# STM32.net
KiCad netlist of a schematic drawn in Altium Designer
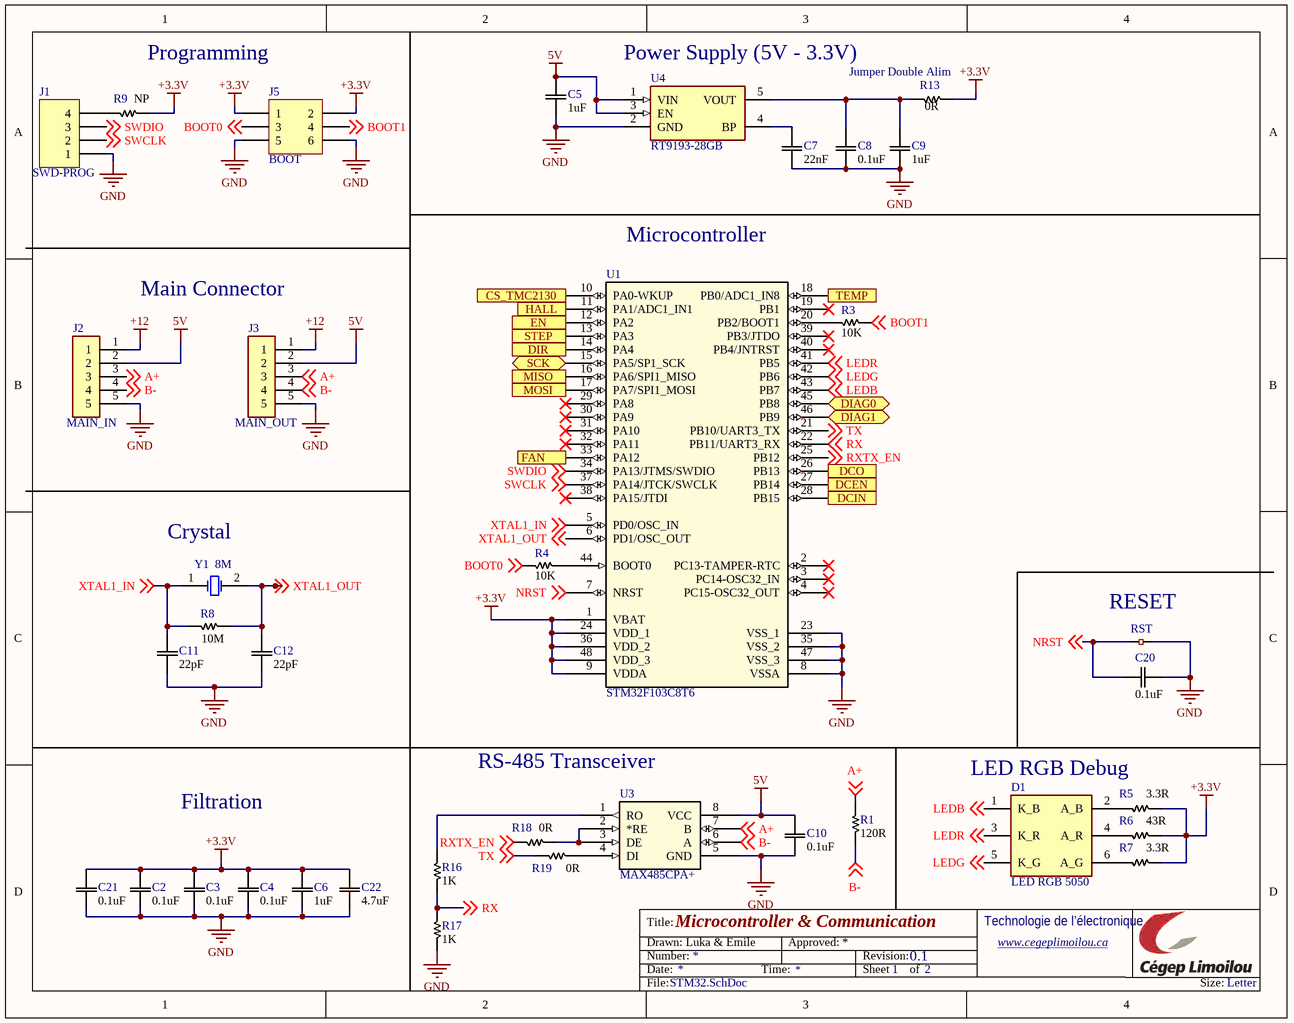
[diagram p0: STM32.SchDoc]

(export (version "E")
  (design (tool "Eeschema 10.0.6"))
  (components
    (comp (ref "C2")
      (value "0.1uF")
      (footprint "0603")
      (description "Capacitor SMD 0603")
      (fields
        (field (name "MANUFACTURER_PART_NUMBER") "12065A820JAT2A")
        (field (name "Comment") "Capacitor SMD")
        (field (name "COPYRIGHT") "Copyright (C) 2018 Accelerated Designs. All rights reserved")
      )
      (libsource (lib "Schematic_Emile") (part "Capacitor SMD"))
    )
    (comp (ref "C3")
      (value "0.1uF")
      (footprint "0603")
      (description "Capacitor SMD 0603")
      (fields
        (field (name "MANUFACTURER_PART_NUMBER") "12065A820JAT2A")
        (field (name "Comment") "Capacitor SMD")
        (field (name "COPYRIGHT") "Copyright (C) 2018 Accelerated Designs. All rights reserved")
      )
      (libsource (lib "Schematic_Emile") (part "Capacitor SMD"))
    )
    (comp (ref "C4")
      (value "0.1uF")
      (footprint "0603")
      (description "Capacitor SMD 0603")
      (fields
        (field (name "MANUFACTURER_PART_NUMBER") "12065A820JAT2A")
        (field (name "Comment") "Capacitor SMD")
        (field (name "COPYRIGHT") "Copyright (C) 2018 Accelerated Designs. All rights reserved")
      )
      (libsource (lib "Schematic_Emile") (part "Capacitor SMD"))
    )
    (comp (ref "C5")
      (value "1uF")
      (footprint "0603")
      (description "Capacitor SMD 0603")
      (fields
        (field (name "MANUFACTURER_PART_NUMBER") "12065A820JAT2A")
        (field (name "Comment") "Capacitor SMD")
        (field (name "COPYRIGHT") "Copyright (C) 2018 Accelerated Designs. All rights reserved")
      )
      (libsource (lib "Schematic_Emile") (part "Capacitor SMD"))
    )
    (comp (ref "C6")
      (value "1uF")
      (footprint "0603")
      (description "Capacitor SMD 0603")
      (fields
        (field (name "MANUFACTURER_PART_NUMBER") "12065A820JAT2A")
        (field (name "Comment") "Capacitor SMD")
        (field (name "COPYRIGHT") "Copyright (C) 2018 Accelerated Designs. All rights reserved")
      )
      (libsource (lib "Schematic_Emile") (part "Capacitor SMD"))
    )
    (comp (ref "C7")
      (value "22nF")
      (footprint "0603")
      (description "Capacitor SMD 0603")
      (fields
        (field (name "MANUFACTURER_PART_NUMBER") "12065A820JAT2A")
        (field (name "Comment") "Capacitor SMD")
        (field (name "COPYRIGHT") "Copyright (C) 2018 Accelerated Designs. All rights reserved")
      )
      (libsource (lib "Schematic_Emile") (part "Capacitor SMD"))
    )
    (comp (ref "C8")
      (value "0.1uF")
      (footprint "0603")
      (description "Capacitor SMD 0603")
      (fields
        (field (name "MANUFACTURER_PART_NUMBER") "12065A820JAT2A")
        (field (name "Comment") "Capacitor SMD")
        (field (name "COPYRIGHT") "Copyright (C) 2018 Accelerated Designs. All rights reserved")
      )
      (libsource (lib "Schematic_Emile") (part "Capacitor SMD"))
    )
    (comp (ref "C9")
      (value "1uF")
      (footprint "0603")
      (description "Capacitor SMD 0603")
      (fields
        (field (name "MANUFACTURER_PART_NUMBER") "12065A820JAT2A")
        (field (name "Comment") "Capacitor SMD")
        (field (name "COPYRIGHT") "Copyright (C) 2018 Accelerated Designs. All rights reserved")
      )
      (libsource (lib "Schematic_Emile") (part "Capacitor SMD"))
    )
    (comp (ref "C10")
      (value "0.1uF")
      (footprint "0603")
      (description "Capacitor SMD 0603")
      (fields
        (field (name "MANUFACTURER_PART_NUMBER") "12065A820JAT2A")
        (field (name "Comment") "Capacitor SMD")
        (field (name "COPYRIGHT") "Copyright (C) 2018 Accelerated Designs. All rights reserved")
      )
      (libsource (lib "Schematic_Emile") (part "Capacitor SMD"))
    )
    (comp (ref "C11")
      (value "22pF")
      (footprint "0603")
      (description "Capacitor SMD 0603")
      (fields
        (field (name "MANUFACTURER_PART_NUMBER") "12065A820JAT2A")
        (field (name "Comment") "Capacitor SMD")
        (field (name "COPYRIGHT") "Copyright (C) 2018 Accelerated Designs. All rights reserved")
      )
      (libsource (lib "Schematic_Emile") (part "Capacitor SMD"))
    )
    (comp (ref "C12")
      (value "22pF")
      (footprint "0603")
      (description "Capacitor SMD 0603")
      (fields
        (field (name "MANUFACTURER_PART_NUMBER") "12065A820JAT2A")
        (field (name "Comment") "Capacitor SMD")
        (field (name "COPYRIGHT") "Copyright (C) 2018 Accelerated Designs. All rights reserved")
      )
      (libsource (lib "Schematic_Emile") (part "Capacitor SMD"))
    )
    (comp (ref "C20")
      (value "0.1uF")
      (footprint "0603")
      (description "Capacitor SMD 0603")
      (fields
        (field (name "MANUFACTURER_PART_NUMBER") "12065A820JAT2A")
        (field (name "Comment") "Capacitor SMD")
        (field (name "COPYRIGHT") "Copyright (C) 2018 Accelerated Designs. All rights reserved")
      )
      (libsource (lib "Schematic_Emile") (part "Capacitor SMD"))
    )
    (comp (ref "C21")
      (value "0.1uF")
      (footprint "0603")
      (description "Capacitor SMD 0603")
      (fields
        (field (name "MANUFACTURER_PART_NUMBER") "12065A820JAT2A")
        (field (name "Comment") "Capacitor SMD")
        (field (name "COPYRIGHT") "Copyright (C) 2018 Accelerated Designs. All rights reserved")
      )
      (libsource (lib "Schematic_Emile") (part "Capacitor SMD"))
    )
    (comp (ref "C22")
      (value "4.7uF")
      (footprint "0603")
      (description "Capacitor SMD 0603")
      (fields
        (field (name "MANUFACTURER_PART_NUMBER") "12065A820JAT2A")
        (field (name "Comment") "Capacitor SMD")
        (field (name "COPYRIGHT") "Copyright (C) 2018 Accelerated Designs. All rights reserved")
      )
      (libsource (lib "Schematic_Emile") (part "Capacitor SMD"))
    )
    (comp (ref "D1")
      (value "LED RGB 5050")
      (footprint "LED 5050")
      (description "LED")
      (fields
        (field (name "MANUFACTURER_PART_NUMBER") "150505M173300")
        (field (name "MOUSER PART NUMBER") "710-150505M173300")
      )
      (libsource (lib "Schematic_Emile") (part "150505M173300"))
    )
    (comp (ref "J1")
      (value "SWD-PROG")
      (footprint "HDR1X4")
      (description "Header, 4-Pin")
      (fields (field (name "PUBLISHER") "Altium Limited"))
      (libsource (lib "Miscellaneous Connectors") (part "Header 4"))
    )
    (comp (ref "J2")
      (value "MAIN_IN")
      (footprint "JST 5POS 2.5mm 90°")
      (description "Connector")
      (fields (field (name "MANUFACTURER_PART_NUMBER") "S5B-XH-A-1(LF)(SN)"))
      (libsource (lib "Schematic_Emile") (part "JST 5POS"))
    )
    (comp (ref "J3")
      (value "MAIN_OUT")
      (footprint "JST 5POS 2.5mm 90°")
      (description "Connector")
      (fields (field (name "MANUFACTURER_PART_NUMBER") "S5B-XH-A-1(LF)(SN)"))
      (libsource (lib "Schematic_Emile") (part "JST 5POS"))
    )
    (comp (ref "J5")
      (value "BOOT")
      (footprint "Header 3x2 1.27mm SMD")
      (description "Header, 3-Pin, Dual row")
      (fields (field (name "PUBLISHER") "Altium Limited"))
      (libsource (lib "Miscellaneous Connectors") (part "Header 3X2"))
    )
    (comp (ref "R1")
      (value "120R")
      (footprint "0603")
      (description "Resistor 0603 SMD")
      (fields
        (field (name "MANUFACTURER_PART_NUMBER") "ERJ8CWFR024V")
        (field (name "Comment") "Resistor 0603")
        (field (name "COPYRIGHT") "Copyright (C) 2018 Accelerated Designs. All rights reserved")
      )
      (libsource (lib "Schematic_Emile") (part "Resistor 0603"))
    )
    (comp (ref "R3")
      (value "10K")
      (footprint "0603")
      (description "Resistor 0603 SMD")
      (fields
        (field (name "MANUFACTURER_PART_NUMBER") "ERJ8CWFR024V")
        (field (name "Comment") "Resistor 0603")
        (field (name "COPYRIGHT") "Copyright (C) 2018 Accelerated Designs. All rights reserved")
      )
      (libsource (lib "Schematic_Emile") (part "Resistor 0603"))
    )
    (comp (ref "R4")
      (value "10K")
      (footprint "0603")
      (description "Resistor 0603 SMD")
      (fields
        (field (name "MANUFACTURER_PART_NUMBER") "ERJ8CWFR024V")
        (field (name "Comment") "Resistor 0603")
        (field (name "COPYRIGHT") "Copyright (C) 2018 Accelerated Designs. All rights reserved")
      )
      (libsource (lib "Schematic_Emile") (part "Resistor 0603"))
    )
    (comp (ref "R5")
      (value "3.3R")
      (footprint "0603")
      (description "Resistor 0603 SMD")
      (fields
        (field (name "MANUFACTURER_PART_NUMBER") "ERJ8CWFR024V")
        (field (name "Comment") "Resistor 0603")
        (field (name "COPYRIGHT") "Copyright (C) 2018 Accelerated Designs. All rights reserved")
      )
      (libsource (lib "Schematic_Emile") (part "Resistor 0603"))
    )
    (comp (ref "R6")
      (value "43R")
      (footprint "0603")
      (description "Resistor 0603 SMD")
      (fields
        (field (name "MANUFACTURER_PART_NUMBER") "ERJ8CWFR024V")
        (field (name "Comment") "Resistor 0603")
        (field (name "COPYRIGHT") "Copyright (C) 2018 Accelerated Designs. All rights reserved")
      )
      (libsource (lib "Schematic_Emile") (part "Resistor 0603"))
    )
    (comp (ref "R7")
      (value "3.3R")
      (footprint "0603")
      (description "Resistor 0603 SMD")
      (fields
        (field (name "MANUFACTURER_PART_NUMBER") "ERJ8CWFR024V")
        (field (name "Comment") "Resistor 0603")
        (field (name "COPYRIGHT") "Copyright (C) 2018 Accelerated Designs. All rights reserved")
      )
      (libsource (lib "Schematic_Emile") (part "Resistor 0603"))
    )
    (comp (ref "R8")
      (value "10M")
      (footprint "0603")
      (description "Resistor 0603 SMD")
      (fields
        (field (name "MANUFACTURER_PART_NUMBER") "ERJ8CWFR024V")
        (field (name "Comment") "Resistor 0603")
        (field (name "COPYRIGHT") "Copyright (C) 2018 Accelerated Designs. All rights reserved")
      )
      (libsource (lib "Schematic_Emile") (part "Resistor 0603"))
    )
    (comp (ref "R9")
      (value "NP")
      (footprint "0603")
      (description "Resistor 0603 SMD")
      (fields
        (field (name "MANUFACTURER_PART_NUMBER") "ERJ8CWFR024V")
        (field (name "Comment") "Resistor 0603")
        (field (name "COPYRIGHT") "Copyright (C) 2018 Accelerated Designs. All rights reserved")
      )
      (libsource (lib "Schematic_Emile") (part "Resistor 0603"))
    )
    (comp (ref "R13")
      (value "0R")
      (footprint "0603")
      (description "Resistor 0603 SMD")
      (fields
        (field (name "MANUFACTURER_PART_NUMBER") "ERJ8CWFR024V")
        (field (name "Comment") "Resistor 0603")
        (field (name "COPYRIGHT") "Copyright (C) 2018 Accelerated Designs. All rights reserved")
      )
      (libsource (lib "Schematic_Emile") (part "Resistor 0603"))
    )
    (comp (ref "R16")
      (value "1K")
      (footprint "0603")
      (description "Resistor 0603 SMD")
      (fields
        (field (name "MANUFACTURER_PART_NUMBER") "ERJ8CWFR024V")
        (field (name "Comment") "Resistor 0603")
        (field (name "COPYRIGHT") "Copyright (C) 2018 Accelerated Designs. All rights reserved")
      )
      (libsource (lib "Schematic_Emile") (part "Resistor 0603"))
    )
    (comp (ref "R17")
      (value "1K")
      (footprint "0603")
      (description "Resistor 0603 SMD")
      (fields
        (field (name "MANUFACTURER_PART_NUMBER") "ERJ8CWFR024V")
        (field (name "Comment") "Resistor 0603")
        (field (name "COPYRIGHT") "Copyright (C) 2018 Accelerated Designs. All rights reserved")
      )
      (libsource (lib "Schematic_Emile") (part "Resistor 0603"))
    )
    (comp (ref "R18")
      (value "0R")
      (footprint "0603")
      (description "Resistor 0603 SMD")
      (fields
        (field (name "MANUFACTURER_PART_NUMBER") "ERJ8CWFR024V")
        (field (name "Comment") "Resistor 0603")
        (field (name "COPYRIGHT") "Copyright (C) 2018 Accelerated Designs. All rights reserved")
      )
      (libsource (lib "Schematic_Emile") (part "Resistor 0603"))
    )
    (comp (ref "R19")
      (value "0R")
      (footprint "0603")
      (description "Resistor 0603 SMD")
      (fields
        (field (name "MANUFACTURER_PART_NUMBER") "ERJ8CWFR024V")
        (field (name "Comment") "Resistor 0603")
        (field (name "COPYRIGHT") "Copyright (C) 2018 Accelerated Designs. All rights reserved")
      )
      (libsource (lib "Schematic_Emile") (part "Resistor 0603"))
    )
    (comp (ref "RST")
      (value "PAD RST")
      (footprint "PAD")
      (description "SMD Pad for contact")
      (libsource (lib "Schematic_Emile") (part "PAD"))
    )
    (comp (ref "U1")
      (value "STM32F103C8T6")
      (footprint "LQFP-48")
      (description "Integrated Circuit STM32")
      (fields (field (name "COPYRIGHT") "Copyright (C) 2018 Accelerated Designs. All rights reserved"))
      (libsource (lib "Schematic_Emile") (part "STM32F103C8T6"))
    )
    (comp (ref "U3")
      (value "MAX485CPA+")
      (footprint "DIP 8 - 3D")
      (description "RS485 Communication")
      (fields (field (name "COPYRIGHT") "Copyright (C) 2018 Accelerated Designs. All rights reserved"))
      (libsource (lib "Schematic_Emile") (part "MAX485CPA+"))
    )
    (comp (ref "U4")
      (value "RT9193-28GB")
      (footprint "SamacSys:SOT94P279X130-5N")
      (description "Voltage Regulator 3.3V")
      (libsource (lib "Schematic_Emile") (part "RT9193-28GB"))
    )
    (comp (ref "Y1")
      (value "8M")
      (footprint "ATS080B-E")
      (description "Crystal Oscillator")
      (fields (field (name "PUBLISHER") "Altium Limited"))
      (libsource (lib "Miscellaneous Devices") (part "XTAL"))
    )
  )
  (nets
    (net (code "1") (name "+3.3V") (class "Default")
      (node (ref "C2") (pin "2") (pinfunction "2_2") (pintype "passive"))
      (node (ref "C21") (pin "2") (pinfunction "2_2") (pintype "passive"))
      (node (ref "C22") (pin "2") (pinfunction "2_2") (pintype "passive"))
      (node (ref "C3") (pin "2") (pinfunction "2_2") (pintype "passive"))
      (node (ref "C4") (pin "2") (pinfunction "2_2") (pintype "passive"))
      (node (ref "C6") (pin "2") (pinfunction "2_2") (pintype "passive"))
      (node (ref "J5") (pin "1") (pinfunction "1_1") (pintype "passive"))
      (node (ref "J5") (pin "2") (pinfunction "2_2") (pintype "passive"))
      (node (ref "R13") (pin "2") (pinfunction "2_2") (pintype "passive"))
      (node (ref "R5") (pin "2") (pinfunction "2_2") (pintype "passive"))
      (node (ref "R6") (pin "2") (pinfunction "2_2") (pintype "passive"))
      (node (ref "R7") (pin "2") (pinfunction "2_2") (pintype "passive"))
      (node (ref "R9") (pin "2") (pinfunction "2_2") (pintype "passive"))
      (node (ref "U1") (pin "1") (pinfunction "VBAT_1") (pintype "power_in"))
      (node (ref "U1") (pin "24") (pinfunction "VDD_1_24") (pintype "power_in"))
      (node (ref "U1") (pin "36") (pinfunction "VDD_2_36") (pintype "power_in"))
      (node (ref "U1") (pin "48") (pinfunction "VDD_3_48") (pintype "power_in"))
      (node (ref "U1") (pin "9") (pinfunction "VDDA_9") (pintype "power_in"))
    )
    (net (code "2") (name "+12") (class "Default")
      (node (ref "J2") (pin "1") (pinfunction "1_1") (pintype "passive"))
      (node (ref "J3") (pin "1") (pinfunction "1_1") (pintype "passive"))
    )
    (net (code "3") (name "/CS_TMC2130") (class "Default")
      (node (ref "U1") (pin "10") (pinfunction "PA0-WKUP_10") (pintype "bidirectional"))
    )
    (net (code "4") (name "/DCEN") (class "Default")
      (node (ref "U1") (pin "27") (pinfunction "PB14_27") (pintype "bidirectional"))
    )
    (net (code "5") (name "/DCIN") (class "Default")
      (node (ref "U1") (pin "28") (pinfunction "PB15_28") (pintype "bidirectional"))
    )
    (net (code "6") (name "/DCO") (class "Default")
      (node (ref "U1") (pin "26") (pinfunction "PB13_26") (pintype "bidirectional"))
    )
    (net (code "7") (name "/DIAG0") (class "Default")
      (node (ref "U1") (pin "45") (pinfunction "PB8_45") (pintype "bidirectional"))
    )
    (net (code "8") (name "/DIAG1") (class "Default")
      (node (ref "U1") (pin "46") (pinfunction "PB9_46") (pintype "bidirectional"))
    )
    (net (code "9") (name "/DIR") (class "Default")
      (node (ref "U1") (pin "14") (pinfunction "PA4_14") (pintype "bidirectional"))
    )
    (net (code "10") (name "/EN") (class "Default")
      (node (ref "U1") (pin "12") (pinfunction "PA2_12") (pintype "bidirectional"))
    )
    (net (code "11") (name "/FAN") (class "Default")
      (node (ref "U1") (pin "33") (pinfunction "PA12_33") (pintype "bidirectional"))
    )
    (net (code "12") (name "/HALL") (class "Default")
      (node (ref "U1") (pin "11") (pinfunction "PA1/ADC1_IN1_11") (pintype "bidirectional"))
    )
    (net (code "13") (name "/MISO") (class "Default")
      (node (ref "U1") (pin "16") (pinfunction "PA6/SPI1_MISO_16") (pintype "bidirectional"))
    )
    (net (code "14") (name "/MOSI") (class "Default")
      (node (ref "U1") (pin "17") (pinfunction "PA7/SPI1_MOSI_17") (pintype "bidirectional"))
    )
    (net (code "15") (name "/SCK") (class "Default")
      (node (ref "U1") (pin "15") (pinfunction "PA5/SP1_SCK_15") (pintype "bidirectional"))
    )
    (net (code "16") (name "/STEP") (class "Default")
      (node (ref "U1") (pin "13") (pinfunction "PA3_13") (pintype "bidirectional"))
    )
    (net (code "17") (name "/TEMP") (class "Default")
      (node (ref "U1") (pin "18") (pinfunction "PB0/ADC1_IN8_18") (pintype "bidirectional"))
    )
    (net (code "18") (name "5V") (class "Default")
      (node (ref "C10") (pin "2") (pinfunction "2_2") (pintype "passive"))
      (node (ref "C5") (pin "2") (pinfunction "2_2") (pintype "passive"))
      (node (ref "J2") (pin "2") (pinfunction "2_2") (pintype "passive"))
      (node (ref "J3") (pin "2") (pinfunction "2_2") (pintype "passive"))
      (node (ref "U3") (pin "8") (pinfunction "VCC_8") (pintype "power_in"))
      (node (ref "U4") (pin "1") (pinfunction "VIN_1") (pintype "input"))
      (node (ref "U4") (pin "3") (pinfunction "EN_3") (pintype "input"))
    )
    (net (code "19") (name "A+") (class "Default")
      (node (ref "J2") (pin "3") (pinfunction "3_3") (pintype "passive"))
      (node (ref "J3") (pin "3") (pinfunction "3_3") (pintype "passive"))
      (node (ref "R1") (pin "2") (pinfunction "2_2") (pintype "passive"))
      (node (ref "U3") (pin "7") (pinfunction "B_7") (pintype "bidirectional"))
    )
    (net (code "20") (name "B-") (class "Default")
      (node (ref "J2") (pin "4") (pinfunction "4_4") (pintype "passive"))
      (node (ref "J3") (pin "4") (pinfunction "4_4") (pintype "passive"))
      (node (ref "R1") (pin "1") (pinfunction "1_1") (pintype "passive"))
      (node (ref "U3") (pin "6") (pinfunction "A_6") (pintype "bidirectional"))
    )
    (net (code "21") (name "BOOT0") (class "Default")
      (node (ref "J5") (pin "3") (pinfunction "3_3") (pintype "passive"))
      (node (ref "R4") (pin "1") (pinfunction "1_1") (pintype "passive"))
    )
    (net (code "22") (name "BOOT1") (class "Default")
      (node (ref "J5") (pin "4") (pinfunction "4_4") (pintype "passive"))
      (node (ref "R3") (pin "2") (pinfunction "2_2") (pintype "passive"))
    )
    (net (code "23") (name "GND") (class "Default")
      (node (ref "C10") (pin "1") (pinfunction "1_1") (pintype "passive"))
      (node (ref "C11") (pin "1") (pinfunction "1_1") (pintype "passive"))
      (node (ref "C12") (pin "1") (pinfunction "1_1") (pintype "passive"))
      (node (ref "C2") (pin "1") (pinfunction "1_1") (pintype "passive"))
      (node (ref "C20") (pin "1") (pinfunction "1_1") (pintype "passive"))
      (node (ref "C21") (pin "1") (pinfunction "1_1") (pintype "passive"))
      (node (ref "C22") (pin "1") (pinfunction "1_1") (pintype "passive"))
      (node (ref "C3") (pin "1") (pinfunction "1_1") (pintype "passive"))
      (node (ref "C4") (pin "1") (pinfunction "1_1") (pintype "passive"))
      (node (ref "C5") (pin "1") (pinfunction "1_1") (pintype "passive"))
      (node (ref "C6") (pin "1") (pinfunction "1_1") (pintype "passive"))
      (node (ref "C7") (pin "1") (pinfunction "1_1") (pintype "passive"))
      (node (ref "C8") (pin "1") (pinfunction "1_1") (pintype "passive"))
      (node (ref "C9") (pin "1") (pinfunction "1_1") (pintype "passive"))
      (node (ref "J1") (pin "1") (pinfunction "1_1") (pintype "passive"))
      (node (ref "J2") (pin "5") (pinfunction "5_5") (pintype "passive"))
      (node (ref "J3") (pin "5") (pinfunction "5_5") (pintype "passive"))
      (node (ref "J5") (pin "5") (pinfunction "5_5") (pintype "passive"))
      (node (ref "J5") (pin "6") (pinfunction "6_6") (pintype "passive"))
      (node (ref "R17") (pin "2") (pinfunction "2_2") (pintype "passive"))
      (node (ref "RST") (pin "1") (pinfunction "1_1") (pintype "passive"))
      (node (ref "U1") (pin "23") (pinfunction "VSS_1_23") (pintype "power_in"))
      (node (ref "U1") (pin "35") (pinfunction "VSS_2_35") (pintype "power_in"))
      (node (ref "U1") (pin "47") (pinfunction "VSS_3_47") (pintype "power_in"))
      (node (ref "U1") (pin "8") (pinfunction "VSSA_8") (pintype "power_in"))
      (node (ref "U3") (pin "5") (pinfunction "GND_5") (pintype "power_in"))
      (node (ref "U4") (pin "2") (pinfunction "GND_2") (pintype "power_in"))
    )
    (net (code "24") (name "LEDB") (class "Default")
      (node (ref "D1") (pin "1") (pinfunction "K_B_1") (pintype "passive"))
      (node (ref "U1") (pin "43") (pinfunction "PB7_43") (pintype "bidirectional"))
    )
    (net (code "25") (name "LEDG") (class "Default")
      (node (ref "D1") (pin "5") (pinfunction "K_G_5") (pintype "passive"))
      (node (ref "U1") (pin "42") (pinfunction "PB6_42") (pintype "bidirectional"))
    )
    (net (code "26") (name "LEDR") (class "Default")
      (node (ref "D1") (pin "3") (pinfunction "K_R_3") (pintype "passive"))
      (node (ref "U1") (pin "41") (pinfunction "PB5_41") (pintype "bidirectional"))
    )
    (net (code "27") (name "NRST") (class "Default")
      (node (ref "C20") (pin "2") (pinfunction "2_2") (pintype "passive"))
      (node (ref "RST") (pin "2") (pinfunction "2_2") (pintype "passive"))
      (node (ref "U1") (pin "7") (pinfunction "NRST_7") (pintype "bidirectional"))
    )
    (net (code "28") (name "Net-(D1-A_B)") (class "Default")
      (node (ref "D1") (pin "2") (pinfunction "A_B_2") (pintype "passive"))
      (node (ref "R5") (pin "1") (pinfunction "1_1") (pintype "passive"))
    )
    (net (code "29") (name "Net-(D1-A_G)") (class "Default")
      (node (ref "D1") (pin "6") (pinfunction "A_G_6") (pintype "passive"))
      (node (ref "R7") (pin "1") (pinfunction "1_1") (pintype "passive"))
    )
    (net (code "30") (name "Net-(D1-A_R)") (class "Default")
      (node (ref "D1") (pin "4") (pinfunction "A_R_4") (pintype "passive"))
      (node (ref "R6") (pin "1") (pinfunction "1_1") (pintype "passive"))
    )
    (net (code "31") (name "Net-(J1-Pad4)") (class "Default")
      (node (ref "J1") (pin "4") (pinfunction "4_4") (pintype "passive"))
      (node (ref "R9") (pin "1") (pinfunction "1_1") (pintype "passive"))
    )
    (net (code "32") (name "Net-(U1-BOOT0)") (class "Default")
      (node (ref "R4") (pin "2") (pinfunction "2_2") (pintype "passive"))
      (node (ref "U1") (pin "44") (pinfunction "BOOT0_44") (pintype "input"))
    )
    (net (code "33") (name "Net-(U1-PB2{slash}BOOT1)") (class "Default")
      (node (ref "R3") (pin "1") (pinfunction "1_1") (pintype "passive"))
      (node (ref "U1") (pin "20") (pinfunction "PB2/BOOT1_20") (pintype "bidirectional"))
    )
    (net (code "34") (name "Net-(U3-*RE)") (class "Default")
      (node (ref "R18") (pin "2") (pinfunction "2_2") (pintype "passive"))
      (node (ref "U3") (pin "2") (pinfunction "*RE_2") (pintype "input"))
      (node (ref "U3") (pin "3") (pinfunction "DE_3") (pintype "input"))
    )
    (net (code "35") (name "Net-(U3-DI)") (class "Default")
      (node (ref "R19") (pin "2") (pinfunction "2_2") (pintype "passive"))
      (node (ref "U3") (pin "4") (pinfunction "DI_4") (pintype "input"))
    )
    (net (code "36") (name "Net-(U3-RO)") (class "Default")
      (node (ref "R16") (pin "1") (pinfunction "1_1") (pintype "passive"))
      (node (ref "U3") (pin "1") (pinfunction "RO_1") (pintype "output"))
    )
    (net (code "37") (name "Net-(U4-BP)") (class "Default")
      (node (ref "C7") (pin "2") (pinfunction "2_2") (pintype "passive"))
      (node (ref "U4") (pin "4") (pinfunction "BP_4") (pintype "passive"))
    )
    (net (code "38") (name "Net-(U4-VOUT)") (class "Default")
      (node (ref "C8") (pin "2") (pinfunction "2_2") (pintype "passive"))
      (node (ref "C9") (pin "2") (pinfunction "2_2") (pintype "passive"))
      (node (ref "R13") (pin "1") (pinfunction "1_1") (pintype "passive"))
      (node (ref "U4") (pin "5") (pinfunction "VOUT_5") (pintype "passive"))
    )
    (net (code "39") (name "RX") (class "Default")
      (node (ref "R16") (pin "2") (pinfunction "2_2") (pintype "passive"))
      (node (ref "R17") (pin "1") (pinfunction "1_1") (pintype "passive"))
      (node (ref "U1") (pin "22") (pinfunction "PB11/UART3_RX_22") (pintype "bidirectional"))
    )
    (net (code "40") (name "RXTX_EN") (class "Default")
      (node (ref "R18") (pin "1") (pinfunction "1_1") (pintype "passive"))
      (node (ref "U1") (pin "25") (pinfunction "PB12_25") (pintype "bidirectional"))
    )
    (net (code "41") (name "SWCLK") (class "Default")
      (node (ref "J1") (pin "2") (pinfunction "2_2") (pintype "passive"))
      (node (ref "U1") (pin "37") (pinfunction "PA14/JTCK/SWCLK_37") (pintype "bidirectional"))
    )
    (net (code "42") (name "SWDIO") (class "Default")
      (node (ref "J1") (pin "3") (pinfunction "3_3") (pintype "passive"))
      (node (ref "U1") (pin "34") (pinfunction "PA13/JTMS/SWDIO_34") (pintype "bidirectional"))
    )
    (net (code "43") (name "TX") (class "Default")
      (node (ref "R19") (pin "1") (pinfunction "1_1") (pintype "passive"))
      (node (ref "U1") (pin "21") (pinfunction "PB10/UART3_TX_21") (pintype "bidirectional"))
    )
    (net (code "44") (name "XTAL1_IN") (class "Default")
      (node (ref "C11") (pin "2") (pinfunction "2_2") (pintype "passive"))
      (node (ref "R8") (pin "1") (pinfunction "1_1") (pintype "passive"))
      (node (ref "U1") (pin "5") (pinfunction "PD0/OSC_IN_5") (pintype "bidirectional"))
      (node (ref "Y1") (pin "1") (pinfunction "OSC1_1") (pintype "passive"))
    )
    (net (code "45") (name "XTAL1_OUT") (class "Default")
      (node (ref "C12") (pin "2") (pinfunction "2_2") (pintype "passive"))
      (node (ref "R8") (pin "2") (pinfunction "2_2") (pintype "passive"))
      (node (ref "U1") (pin "6") (pinfunction "PD1/OSC_OUT_6") (pintype "bidirectional"))
      (node (ref "Y1") (pin "2") (pinfunction "OSC2_2") (pintype "passive"))
    )
    (net (code "46") (name "unconnected-(U1-PA8-Pad29)") (class "Default")
      (node (ref "U1") (pin "29") (pinfunction "PA8_29") (pintype "bidirectional+no_connect"))
    )
    (net (code "47") (name "unconnected-(U1-PA9-Pad30)") (class "Default")
      (node (ref "U1") (pin "30") (pinfunction "PA9_30") (pintype "bidirectional+no_connect"))
    )
    (net (code "48") (name "unconnected-(U1-PA10-Pad31)") (class "Default")
      (node (ref "U1") (pin "31") (pinfunction "PA10_31") (pintype "bidirectional+no_connect"))
    )
    (net (code "49") (name "unconnected-(U1-PA11-Pad32)") (class "Default")
      (node (ref "U1") (pin "32") (pinfunction "PA11_32") (pintype "bidirectional+no_connect"))
    )
    (net (code "50") (name "unconnected-(U1-PA15{slash}JTDI-Pad38)") (class "Default")
      (node (ref "U1") (pin "38") (pinfunction "PA15/JTDI_38") (pintype "bidirectional+no_connect"))
    )
    (net (code "51") (name "unconnected-(U1-PB1-Pad19)") (class "Default")
      (node (ref "U1") (pin "19") (pinfunction "PB1_19") (pintype "bidirectional+no_connect"))
    )
    (net (code "52") (name "unconnected-(U1-PB3{slash}JTDO-Pad39)") (class "Default")
      (node (ref "U1") (pin "39") (pinfunction "PB3/JTDO_39") (pintype "bidirectional+no_connect"))
    )
    (net (code "53") (name "unconnected-(U1-PB4{slash}JNTRST-Pad40)") (class "Default")
      (node (ref "U1") (pin "40") (pinfunction "PB4/JNTRST_40") (pintype "bidirectional+no_connect"))
    )
    (net (code "54") (name "unconnected-(U1-PC13-TAMPER-RTC-Pad2)") (class "Default")
      (node (ref "U1") (pin "2") (pinfunction "PC13-TAMPER-RTC_2") (pintype "bidirectional+no_connect"))
    )
    (net (code "55") (name "unconnected-(U1-PC14-OSC32_IN-Pad3)") (class "Default")
      (node (ref "U1") (pin "3") (pinfunction "PC14-OSC32_IN_3") (pintype "bidirectional+no_connect"))
    )
    (net (code "56") (name "unconnected-(U1-PC15-OSC32_OUT-Pad4)") (class "Default")
      (node (ref "U1") (pin "4") (pinfunction "PC15-OSC32_OUT_4") (pintype "bidirectional+no_connect"))
    )
  )
)
